# EDU_High-Speed-Design_Ethernet.net
KiCad netlist of a schematic drawn in Altium Designer
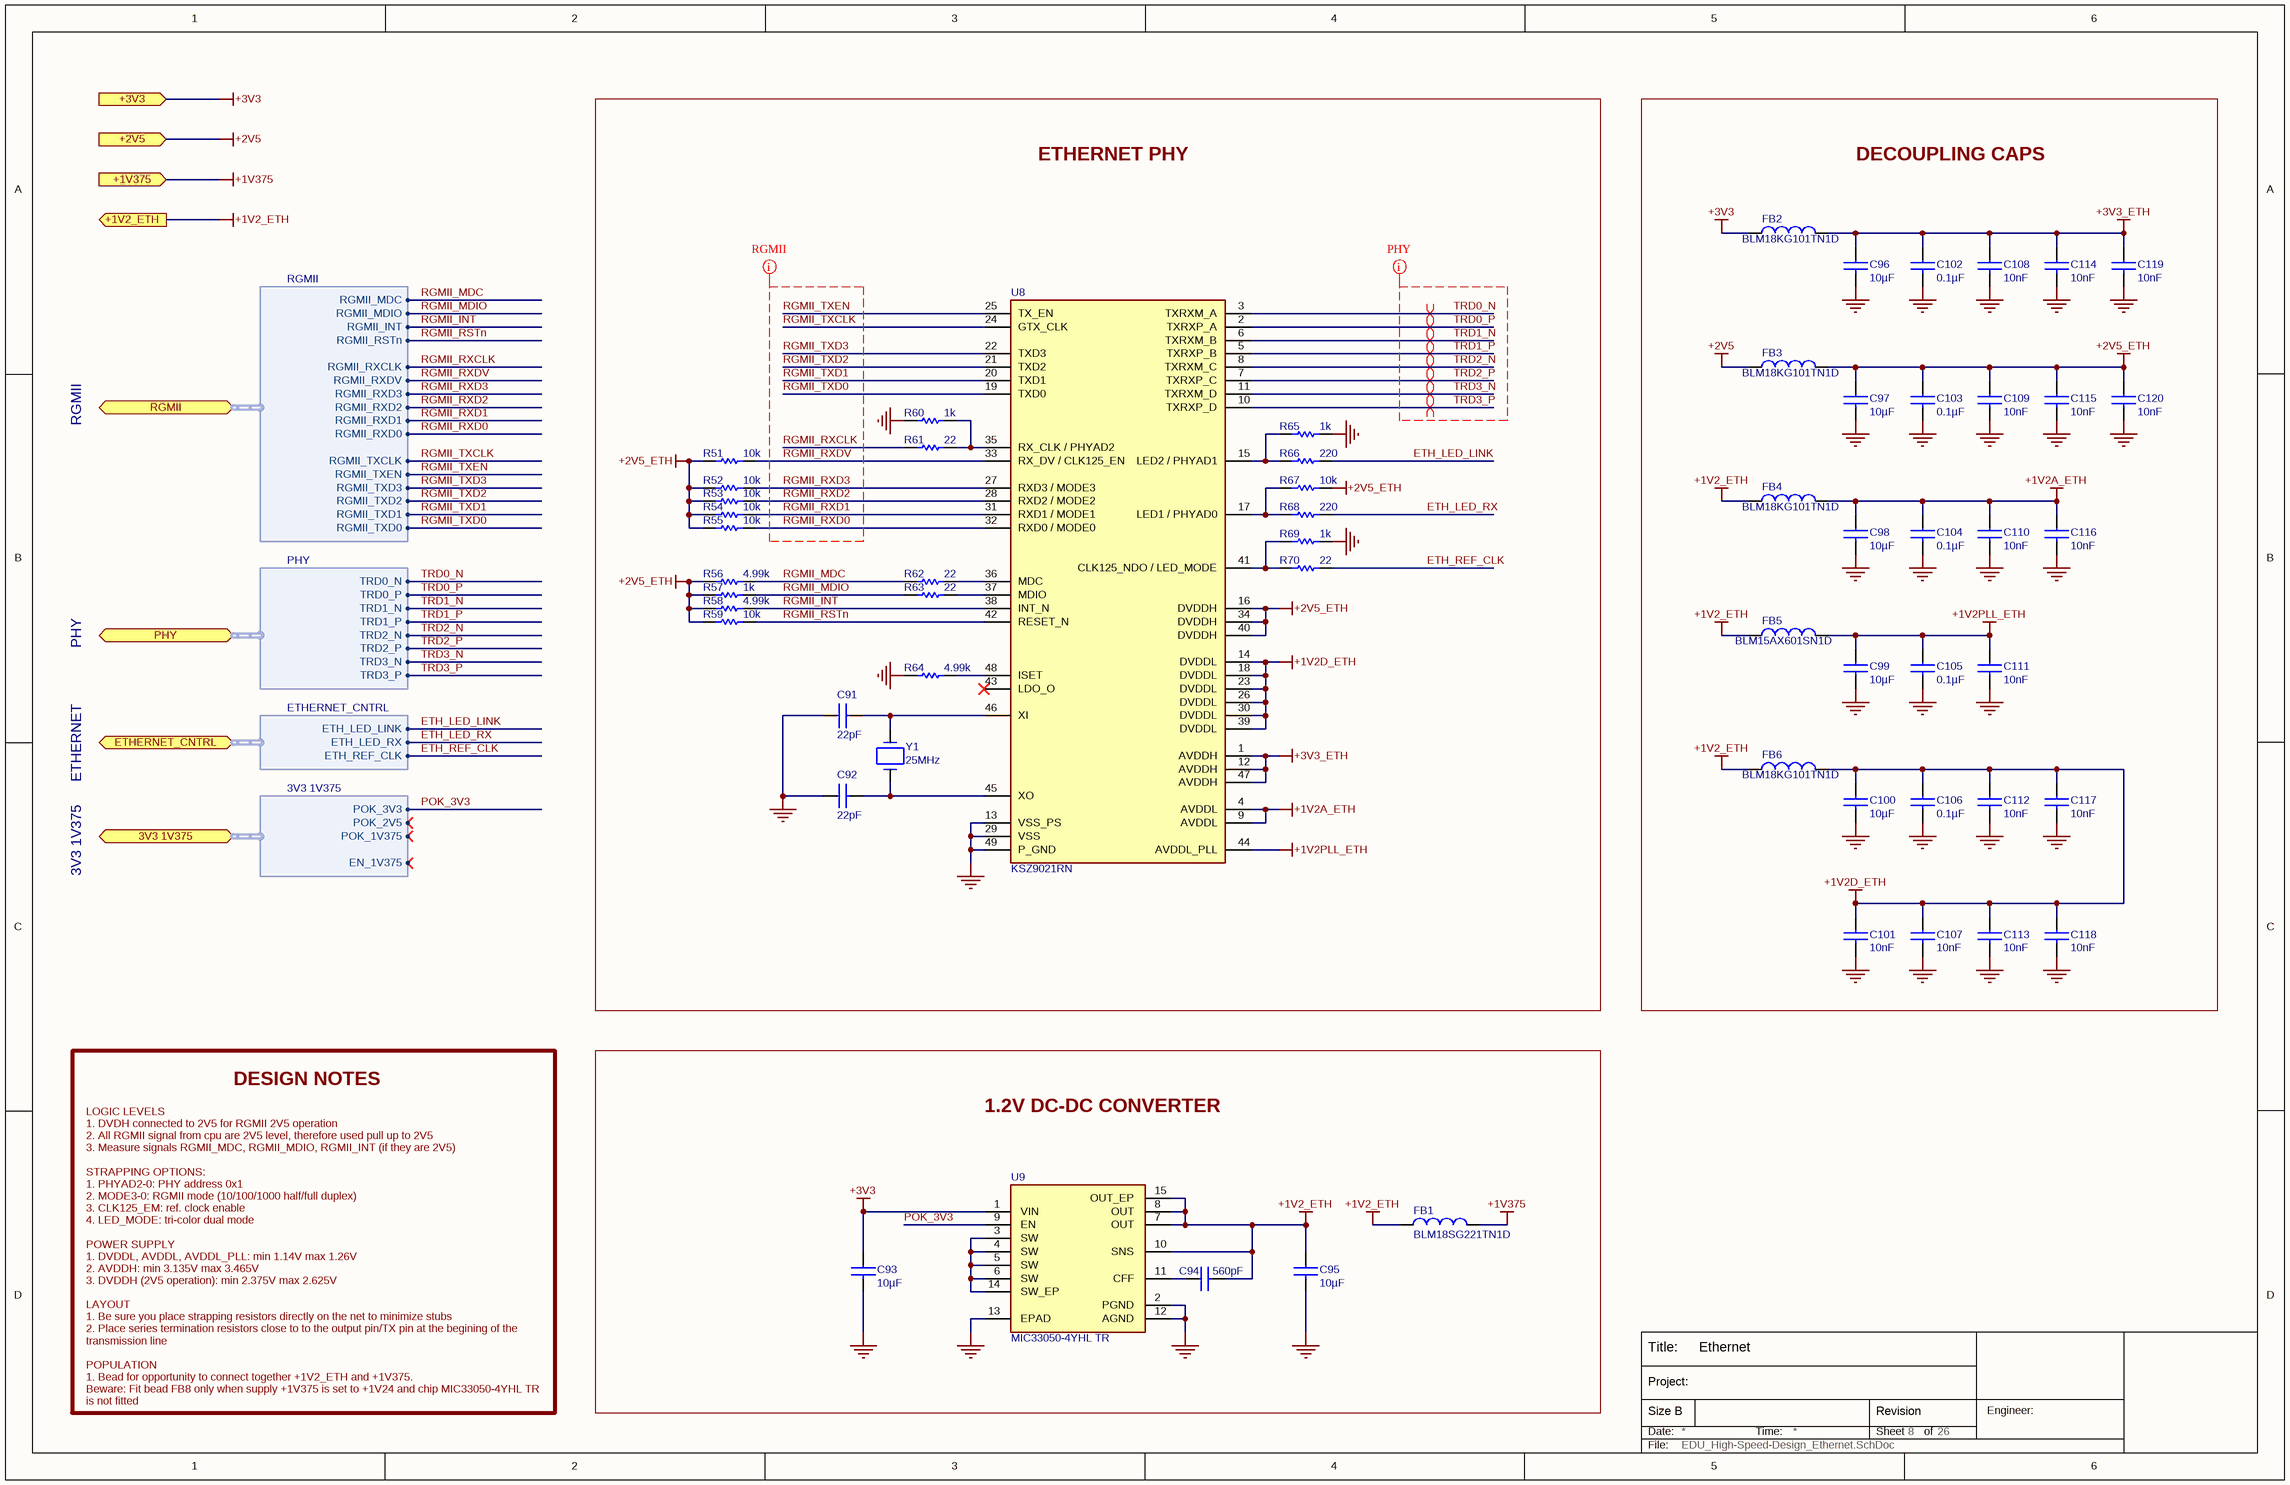
[diagram p0: EDU_High-Speed-Design_Ethernet.SchDoc]

(export (version "E")
  (design (tool "Eeschema 10.0.6"))
  (components
    (comp (ref "C91")
      (value "22pF")
      (footprint "C0402")
      (description "CAP CER 22PF 50V C0G 5% 0402")
      (fields (field (name "VOLTAGE") "50V"))
      (libsource (lib "EDU_High-Speed-Design") (part "C1005C0G1H220J"))
    )
    (comp (ref "C92")
      (value "22pF")
      (footprint "C0402")
      (description "CAP CER 22PF 50V C0G 5% 0402")
      (fields (field (name "VOLTAGE") "50V"))
      (libsource (lib "EDU_High-Speed-Design") (part "C1005C0G1H220J"))
    )
    (comp (ref "C93")
      (value "10µF")
      (footprint "C0603")
      (description "CAP CER 10UF 6.3V X5R 20% 0603")
      (fields (field (name "VOLTAGE") "6.3V"))
      (libsource (lib "EDU_High-Speed-Design") (part "C1608X5R0J106M"))
    )
    (comp (ref "C94")
      (value "560pF")
      (footprint "C0402")
      (description "CAP CER 560PF 50V C0G 0402")
      (fields (field (name "VOLTAGE") "50V"))
      (libsource (lib "EDU_High-Speed-Design") (part "GRM1555C1H561JA01D"))
    )
    (comp (ref "C95")
      (value "10µF")
      (footprint "C0603")
      (description "CAP CER 10UF 6.3V X5R 20% 0603")
      (fields (field (name "VOLTAGE") "6.3V"))
      (libsource (lib "EDU_High-Speed-Design") (part "C1608X5R0J106M"))
    )
    (comp (ref "C96")
      (value "10µF")
      (footprint "C0603")
      (description "CAP CER 10UF 6.3V X5R 20% 0603")
      (fields (field (name "VOLTAGE") "6.3V"))
      (libsource (lib "EDU_High-Speed-Design") (part "C1608X5R0J106M"))
    )
    (comp (ref "C97")
      (value "10µF")
      (footprint "C0603")
      (description "CAP CER 10UF 6.3V X5R 20% 0603")
      (fields (field (name "VOLTAGE") "6.3V"))
      (libsource (lib "EDU_High-Speed-Design") (part "C1608X5R0J106M"))
    )
    (comp (ref "C98")
      (value "10µF")
      (footprint "C0603")
      (description "CAP CER 10UF 6.3V X5R 20% 0603")
      (fields (field (name "VOLTAGE") "6.3V"))
      (libsource (lib "EDU_High-Speed-Design") (part "C1608X5R0J106M"))
    )
    (comp (ref "C99")
      (value "10µF")
      (footprint "C0603")
      (description "CAP CER 10UF 6.3V X5R 20% 0603")
      (fields (field (name "VOLTAGE") "6.3V"))
      (libsource (lib "EDU_High-Speed-Design") (part "C1608X5R0J106M"))
    )
    (comp (ref "C100")
      (value "10µF")
      (footprint "C0603")
      (description "CAP CER 10UF 6.3V X5R 20% 0603")
      (fields (field (name "VOLTAGE") "6.3V"))
      (libsource (lib "EDU_High-Speed-Design") (part "C1608X5R0J106M"))
    )
    (comp (ref "C101")
      (value "10nF")
      (footprint "C0402")
      (description "CAP CER 10000PF 16V X7R 10% 0402")
      (fields
        (field (name "MANUFACTURER") "TDK Corporation")
        (field (name "MANUFACTURER PART NUMBER") "C1005X7R1C103K")
      )
      (libsource (lib "EDU_High-Speed-Design") (part "C1005X7R1C103K"))
    )
    (comp (ref "C102")
      (value "0.1µF")
      (footprint "C0402")
      (description "CAP CER .10UF 50V X5R 10% 0402")
      (fields (field (name "VOLTAGE") "50V"))
      (libsource (lib "EDU_High-Speed-Design") (part "C1005X5R1H104K"))
    )
    (comp (ref "C103")
      (value "0.1µF")
      (footprint "C0402")
      (description "CAP CER .10UF 50V X5R 10% 0402")
      (fields (field (name "VOLTAGE") "50V"))
      (libsource (lib "EDU_High-Speed-Design") (part "C1005X5R1H104K"))
    )
    (comp (ref "C104")
      (value "0.1µF")
      (footprint "C0402")
      (description "CAP CER .10UF 50V X5R 10% 0402")
      (fields (field (name "VOLTAGE") "50V"))
      (libsource (lib "EDU_High-Speed-Design") (part "C1005X5R1H104K"))
    )
    (comp (ref "C105")
      (value "0.1µF")
      (footprint "C0402")
      (description "CAP CER .10UF 50V X5R 10% 0402")
      (fields (field (name "VOLTAGE") "50V"))
      (libsource (lib "EDU_High-Speed-Design") (part "C1005X5R1H104K"))
    )
    (comp (ref "C106")
      (value "0.1µF")
      (footprint "C0402")
      (description "CAP CER .10UF 50V X5R 10% 0402")
      (fields (field (name "VOLTAGE") "50V"))
      (libsource (lib "EDU_High-Speed-Design") (part "C1005X5R1H104K"))
    )
    (comp (ref "C107")
      (value "10nF")
      (footprint "C0402")
      (description "CAP CER 10000PF 16V X7R 10% 0402")
      (fields
        (field (name "MANUFACTURER") "TDK Corporation")
        (field (name "MANUFACTURER PART NUMBER") "C1005X7R1C103K")
      )
      (libsource (lib "EDU_High-Speed-Design") (part "C1005X7R1C103K"))
    )
    (comp (ref "C108")
      (value "10nF")
      (footprint "C0402")
      (description "CAP CER 10000PF 16V X7R 10% 0402")
      (fields
        (field (name "MANUFACTURER") "TDK Corporation")
        (field (name "MANUFACTURER PART NUMBER") "C1005X7R1C103K")
      )
      (libsource (lib "EDU_High-Speed-Design") (part "C1005X7R1C103K"))
    )
    (comp (ref "C109")
      (value "10nF")
      (footprint "C0402")
      (description "CAP CER 10000PF 16V X7R 10% 0402")
      (fields
        (field (name "MANUFACTURER") "TDK Corporation")
        (field (name "MANUFACTURER PART NUMBER") "C1005X7R1C103K")
      )
      (libsource (lib "EDU_High-Speed-Design") (part "C1005X7R1C103K"))
    )
    (comp (ref "C110")
      (value "10nF")
      (footprint "C0402")
      (description "CAP CER 10000PF 16V X7R 10% 0402")
      (fields
        (field (name "MANUFACTURER") "TDK Corporation")
        (field (name "MANUFACTURER PART NUMBER") "C1005X7R1C103K")
      )
      (libsource (lib "EDU_High-Speed-Design") (part "C1005X7R1C103K"))
    )
    (comp (ref "C111")
      (value "10nF")
      (footprint "C0402")
      (description "CAP CER 10000PF 16V X7R 10% 0402")
      (fields
        (field (name "MANUFACTURER") "TDK Corporation")
        (field (name "MANUFACTURER PART NUMBER") "C1005X7R1C103K")
      )
      (libsource (lib "EDU_High-Speed-Design") (part "C1005X7R1C103K"))
    )
    (comp (ref "C112")
      (value "10nF")
      (footprint "C0402")
      (description "CAP CER 10000PF 16V X7R 10% 0402")
      (fields
        (field (name "MANUFACTURER") "TDK Corporation")
        (field (name "MANUFACTURER PART NUMBER") "C1005X7R1C103K")
      )
      (libsource (lib "EDU_High-Speed-Design") (part "C1005X7R1C103K"))
    )
    (comp (ref "C113")
      (value "10nF")
      (footprint "C0402")
      (description "CAP CER 10000PF 16V X7R 10% 0402")
      (fields
        (field (name "MANUFACTURER") "TDK Corporation")
        (field (name "MANUFACTURER PART NUMBER") "C1005X7R1C103K")
      )
      (libsource (lib "EDU_High-Speed-Design") (part "C1005X7R1C103K"))
    )
    (comp (ref "C114")
      (value "10nF")
      (footprint "C0402")
      (description "CAP CER 10000PF 16V X7R 10% 0402")
      (fields
        (field (name "MANUFACTURER") "TDK Corporation")
        (field (name "MANUFACTURER PART NUMBER") "C1005X7R1C103K")
      )
      (libsource (lib "EDU_High-Speed-Design") (part "C1005X7R1C103K"))
    )
    (comp (ref "C115")
      (value "10nF")
      (footprint "C0402")
      (description "CAP CER 10000PF 16V X7R 10% 0402")
      (fields
        (field (name "MANUFACTURER") "TDK Corporation")
        (field (name "MANUFACTURER PART NUMBER") "C1005X7R1C103K")
      )
      (libsource (lib "EDU_High-Speed-Design") (part "C1005X7R1C103K"))
    )
    (comp (ref "C116")
      (value "10nF")
      (footprint "C0402")
      (description "CAP CER 10000PF 16V X7R 10% 0402")
      (fields
        (field (name "MANUFACTURER") "TDK Corporation")
        (field (name "MANUFACTURER PART NUMBER") "C1005X7R1C103K")
      )
      (libsource (lib "EDU_High-Speed-Design") (part "C1005X7R1C103K"))
    )
    (comp (ref "C117")
      (value "10nF")
      (footprint "C0402")
      (description "CAP CER 10000PF 16V X7R 10% 0402")
      (fields
        (field (name "MANUFACTURER") "TDK Corporation")
        (field (name "MANUFACTURER PART NUMBER") "C1005X7R1C103K")
      )
      (libsource (lib "EDU_High-Speed-Design") (part "C1005X7R1C103K"))
    )
    (comp (ref "C118")
      (value "10nF")
      (footprint "C0402")
      (description "CAP CER 10000PF 16V X7R 10% 0402")
      (fields
        (field (name "MANUFACTURER") "TDK Corporation")
        (field (name "MANUFACTURER PART NUMBER") "C1005X7R1C103K")
      )
      (libsource (lib "EDU_High-Speed-Design") (part "C1005X7R1C103K"))
    )
    (comp (ref "C119")
      (value "10nF")
      (footprint "C0402")
      (description "CAP CER 10000PF 16V X7R 10% 0402")
      (fields
        (field (name "MANUFACTURER") "TDK Corporation")
        (field (name "MANUFACTURER PART NUMBER") "C1005X7R1C103K")
      )
      (libsource (lib "EDU_High-Speed-Design") (part "C1005X7R1C103K"))
    )
    (comp (ref "C120")
      (value "10nF")
      (footprint "C0402")
      (description "CAP CER 10000PF 16V X7R 10% 0402")
      (fields
        (field (name "MANUFACTURER") "TDK Corporation")
        (field (name "MANUFACTURER PART NUMBER") "C1005X7R1C103K")
      )
      (libsource (lib "EDU_High-Speed-Design") (part "C1005X7R1C103K"))
    )
    (comp (ref "FB1")
      (value "BLM18SG221TN1D")
      (footprint "L0603")
      (description "FERRITE CHIP 220 OHM 2500MA 0603")
      (libsource (lib "EDU_High-Speed-Design") (part "BLM18SG221TN1D"))
    )
    (comp (ref "FB2")
      (value "BLM18KG101TN1D")
      (footprint "L0603")
      (description "FERRITE CHIP 100 OHM BEAD 0603 3A")
      (libsource (lib "EDU_High-Speed-Design") (part "BLM18KG101TN1D"))
    )
    (comp (ref "FB3")
      (value "BLM18KG101TN1D")
      (footprint "L0603")
      (description "FERRITE CHIP 100 OHM BEAD 0603 3A")
      (libsource (lib "EDU_High-Speed-Design") (part "BLM18KG101TN1D"))
    )
    (comp (ref "FB4")
      (value "BLM18KG101TN1D")
      (footprint "L0603")
      (description "FERRITE CHIP 100 OHM BEAD 0603 3A")
      (libsource (lib "EDU_High-Speed-Design") (part "BLM18KG101TN1D"))
    )
    (comp (ref "FB5")
      (value "BLM15AX601SN1D")
      (footprint "L0402")
      (description "FERRITE CHIP 600 OHM 0402 420mA")
      (libsource (lib "EDU_High-Speed-Design") (part "BLM15AX601SN1D"))
    )
    (comp (ref "FB6")
      (value "BLM18KG101TN1D")
      (footprint "L0603")
      (description "FERRITE CHIP 100 OHM BEAD 0603 3A")
      (libsource (lib "EDU_High-Speed-Design") (part "BLM18KG101TN1D"))
    )
    (comp (ref "R51")
      (value "10k")
      (footprint "R0402")
      (description "RES 10.0K OHM 1/16W 1% 0402 SMD")
      (libsource (lib "EDU_High-Speed-Design") (part "RC0402FR-0710KL"))
    )
    (comp (ref "R52")
      (value "10k")
      (footprint "R0402")
      (description "RES 10.0K OHM 1/16W 1% 0402 SMD")
      (libsource (lib "EDU_High-Speed-Design") (part "RC0402FR-0710KL"))
    )
    (comp (ref "R53")
      (value "10k")
      (footprint "R0402")
      (description "RES 10.0K OHM 1/16W 1% 0402 SMD")
      (libsource (lib "EDU_High-Speed-Design") (part "RC0402FR-0710KL"))
    )
    (comp (ref "R54")
      (value "10k")
      (footprint "R0402")
      (description "RES 10.0K OHM 1/16W 1% 0402 SMD")
      (libsource (lib "EDU_High-Speed-Design") (part "RC0402FR-0710KL"))
    )
    (comp (ref "R55")
      (value "10k")
      (footprint "R0402")
      (description "RES 10.0K OHM 1/16W 1% 0402 SMD")
      (libsource (lib "EDU_High-Speed-Design") (part "RC0402FR-0710KL"))
    )
    (comp (ref "R56")
      (value "4.99k")
      (footprint "R0402")
      (description "RES TF 4.99K OHM 1% 1/16W 0402")
      (libsource (lib "EDU_High-Speed-Design") (part "RMCF0402FT4K99"))
    )
    (comp (ref "R57")
      (value "1k")
      (footprint "R0402")
      (description "RES 1.00K OHM 1/16W 1% 0402 SMD")
      (libsource (lib "EDU_High-Speed-Design") (part "RC0402FR-071KL"))
    )
    (comp (ref "R58")
      (value "4.99k")
      (footprint "R0402")
      (description "RES TF 4.99K OHM 1% 1/16W 0402")
      (libsource (lib "EDU_High-Speed-Design") (part "RMCF0402FT4K99"))
    )
    (comp (ref "R59")
      (value "10k")
      (footprint "R0402")
      (description "RES 10.0K OHM 1/16W 1% 0402 SMD")
      (libsource (lib "EDU_High-Speed-Design") (part "RC0402FR-0710KL"))
    )
    (comp (ref "R60")
      (value "1k")
      (footprint "R0402")
      (description "RES 1.00K OHM 1/16W 1% 0402 SMD")
      (libsource (lib "EDU_High-Speed-Design") (part "RC0402FR-071KL"))
    )
    (comp (ref "R61")
      (value "22")
      (footprint "R0402")
      (description "RES 22.0 OHM 1/16W 1% 0402 SMD")
      (libsource (lib "EDU_High-Speed-Design") (part "RC0402FR-0722RL"))
    )
    (comp (ref "R62")
      (value "22")
      (footprint "R0402")
      (description "RES 22.0 OHM 1/16W 1% 0402 SMD")
      (libsource (lib "EDU_High-Speed-Design") (part "RC0402FR-0722RL"))
    )
    (comp (ref "R63")
      (value "22")
      (footprint "R0402")
      (description "RES 22.0 OHM 1/16W 1% 0402 SMD")
      (libsource (lib "EDU_High-Speed-Design") (part "RC0402FR-0722RL"))
    )
    (comp (ref "R64")
      (value "4.99k")
      (footprint "R0402")
      (description "RES TF 4.99K OHM 1% 1/16W 0402")
      (libsource (lib "EDU_High-Speed-Design") (part "RMCF0402FT4K99"))
    )
    (comp (ref "R65")
      (value "1k")
      (footprint "R0402")
      (description "RES 1.00K OHM 1/16W 1% 0402 SMD")
      (libsource (lib "EDU_High-Speed-Design") (part "RC0402FR-071KL"))
    )
    (comp (ref "R66")
      (value "220")
      (footprint "R0402")
      (description "RES 220 OHM 1/16W 1% 0402 SMD")
      (libsource (lib "EDU_High-Speed-Design") (part "RC0402FR-07220RL"))
    )
    (comp (ref "R67")
      (value "10k")
      (footprint "R0402")
      (description "RES 10.0K OHM 1/16W 1% 0402 SMD")
      (libsource (lib "EDU_High-Speed-Design") (part "RC0402FR-0710KL"))
    )
    (comp (ref "R68")
      (value "220")
      (footprint "R0402")
      (description "RES 220 OHM 1/16W 1% 0402 SMD")
      (libsource (lib "EDU_High-Speed-Design") (part "RC0402FR-07220RL"))
    )
    (comp (ref "R69")
      (value "1k")
      (footprint "R0402")
      (description "RES 1.00K OHM 1/16W 1% 0402 SMD")
      (libsource (lib "EDU_High-Speed-Design") (part "RC0402FR-071KL"))
    )
    (comp (ref "R70")
      (value "22")
      (footprint "R0402")
      (description "RES 22.0 OHM 1/16W 1% 0402 SMD")
      (libsource (lib "EDU_High-Speed-Design") (part "RC0402FR-0722RL"))
    )
    (comp (ref "U8")
      (value "KSZ9021RN")
      (footprint "KSZ9021RN")
      (description "IC TXRX 10/100/1000 SGL 48QFN")
      (libsource (lib "EDU_High-Speed-Design") (part "KSZ9021RN"))
    )
    (comp (ref "U9")
      (value "MIC33050-4YHL TR")
      (footprint "MIC33050-4YHL TR")
      (description "IC PWM REG 600mA 1.2V 12-MLF")
      (libsource (lib "EDU_High-Speed-Design") (part "MIC33050-4YHL TR"))
    )
    (comp (ref "Y1")
      (value "25MHz")
      (footprint "ABM7")
      (description "CRYSTAL 25.0000 MHZ 18PF SMD")
      (libsource (lib "EDU_High-Speed-Design") (part "ABM7-25.000MHZ-D-2-Y-T V1.1"))
    )
  )
  (nets
    (net (code "6") (name "+1V2A_ETH") (class "Default")
      (node (ref "C104") (pin "1") (pinfunction "1_1") (pintype "passive"))
      (node (ref "C110") (pin "1") (pinfunction "1_1") (pintype "passive"))
      (node (ref "C116") (pin "1") (pinfunction "1_1") (pintype "passive"))
      (node (ref "C98") (pin "1") (pinfunction "1_1") (pintype "passive"))
      (node (ref "FB4") (pin "2") (pinfunction "2_2") (pintype "passive"))
      (node (ref "U8") (pin "4") (pinfunction "AVDDL_4") (pintype "passive"))
      (node (ref "U8") (pin "9") (pinfunction "AVDDL_9") (pintype "passive"))
    )
    (net (code "7") (name "+1V2D_ETH") (class "Default")
      (node (ref "C100") (pin "1") (pinfunction "1_1") (pintype "passive"))
      (node (ref "C101") (pin "1") (pinfunction "1_1") (pintype "passive"))
      (node (ref "C106") (pin "1") (pinfunction "1_1") (pintype "passive"))
      (node (ref "C107") (pin "1") (pinfunction "1_1") (pintype "passive"))
      (node (ref "C112") (pin "1") (pinfunction "1_1") (pintype "passive"))
      (node (ref "C113") (pin "1") (pinfunction "1_1") (pintype "passive"))
      (node (ref "C117") (pin "1") (pinfunction "1_1") (pintype "passive"))
      (node (ref "C118") (pin "1") (pinfunction "1_1") (pintype "passive"))
      (node (ref "FB6") (pin "2") (pinfunction "2_2") (pintype "passive"))
      (node (ref "U8") (pin "14") (pinfunction "DVDDL_14") (pintype "passive"))
      (node (ref "U8") (pin "18") (pinfunction "DVDDL_18") (pintype "passive"))
      (node (ref "U8") (pin "23") (pinfunction "DVDDL_23") (pintype "passive"))
      (node (ref "U8") (pin "26") (pinfunction "DVDDL_26") (pintype "passive"))
      (node (ref "U8") (pin "30") (pinfunction "DVDDL_30") (pintype "passive"))
      (node (ref "U8") (pin "39") (pinfunction "DVDDL_39") (pintype "passive"))
    )
    (net (code "8") (name "+1V2PLL_ETH") (class "Default")
      (node (ref "C105") (pin "1") (pinfunction "1_1") (pintype "passive"))
      (node (ref "C111") (pin "1") (pinfunction "1_1") (pintype "passive"))
      (node (ref "C99") (pin "1") (pinfunction "1_1") (pintype "passive"))
      (node (ref "FB5") (pin "2") (pinfunction "2_2") (pintype "passive"))
      (node (ref "U8") (pin "44") (pinfunction "AVDDL_PLL_44") (pintype "passive"))
    )
    (net (code "9") (name "+1V2_ETH") (class "Default")
      (node (ref "C94") (pin "2") (pinfunction "2_2") (pintype "passive"))
      (node (ref "C95") (pin "1") (pinfunction "1_1") (pintype "passive"))
      (node (ref "FB1") (pin "1") (pinfunction "1_1") (pintype "passive"))
      (node (ref "FB4") (pin "1") (pinfunction "1_1") (pintype "passive"))
      (node (ref "FB5") (pin "1") (pinfunction "1_1") (pintype "passive"))
      (node (ref "FB6") (pin "1") (pinfunction "1_1") (pintype "passive"))
      (node (ref "U9") (pin "10") (pinfunction "SNS_10") (pintype "passive"))
      (node (ref "U9") (pin "15") (pinfunction "OUT_EP_15") (pintype "passive"))
      (node (ref "U9") (pin "7") (pinfunction "OUT_7") (pintype "passive"))
      (node (ref "U9") (pin "8") (pinfunction "OUT_8") (pintype "passive"))
    )
    (net (code "10") (name "+1V375") (class "Default")
      (node (ref "FB1") (pin "2") (pinfunction "2_2") (pintype "passive"))
    )
    (net (code "11") (name "+2V5") (class "Default")
      (node (ref "FB3") (pin "1") (pinfunction "1_1") (pintype "passive"))
    )
    (net (code "12") (name "+2V5_ETH") (class "Default")
      (node (ref "C103") (pin "1") (pinfunction "1_1") (pintype "passive"))
      (node (ref "C109") (pin "1") (pinfunction "1_1") (pintype "passive"))
      (node (ref "C115") (pin "1") (pinfunction "1_1") (pintype "passive"))
      (node (ref "C120") (pin "1") (pinfunction "1_1") (pintype "passive"))
      (node (ref "C97") (pin "1") (pinfunction "1_1") (pintype "passive"))
      (node (ref "FB3") (pin "2") (pinfunction "2_2") (pintype "passive"))
      (node (ref "R51") (pin "1") (pinfunction "1_1") (pintype "passive"))
      (node (ref "R52") (pin "1") (pinfunction "1_1") (pintype "passive"))
      (node (ref "R53") (pin "1") (pinfunction "1_1") (pintype "passive"))
      (node (ref "R54") (pin "1") (pinfunction "1_1") (pintype "passive"))
      (node (ref "R55") (pin "1") (pinfunction "1_1") (pintype "passive"))
      (node (ref "R56") (pin "2") (pinfunction "2_2") (pintype "passive"))
      (node (ref "R57") (pin "2") (pinfunction "2_2") (pintype "passive"))
      (node (ref "R58") (pin "2") (pinfunction "2_2") (pintype "passive"))
      (node (ref "R59") (pin "1") (pinfunction "1_1") (pintype "passive"))
      (node (ref "R67") (pin "2") (pinfunction "2_2") (pintype "passive"))
      (node (ref "U8") (pin "16") (pinfunction "DVDDH_16") (pintype "passive"))
      (node (ref "U8") (pin "34") (pinfunction "DVDDH_34") (pintype "passive"))
      (node (ref "U8") (pin "40") (pinfunction "DVDDH_40") (pintype "passive"))
    )
    (net (code "13") (name "+3V3") (class "Default")
      (node (ref "C93") (pin "1") (pinfunction "1_1") (pintype "passive"))
      (node (ref "FB2") (pin "1") (pinfunction "1_1") (pintype "passive"))
      (node (ref "U9") (pin "1") (pinfunction "VIN_1") (pintype "passive"))
    )
    (net (code "14") (name "+3V3_ETH") (class "Default")
      (node (ref "C102") (pin "1") (pinfunction "1_1") (pintype "passive"))
      (node (ref "C108") (pin "1") (pinfunction "1_1") (pintype "passive"))
      (node (ref "C114") (pin "1") (pinfunction "1_1") (pintype "passive"))
      (node (ref "C119") (pin "1") (pinfunction "1_1") (pintype "passive"))
      (node (ref "C96") (pin "1") (pinfunction "1_1") (pintype "passive"))
      (node (ref "FB2") (pin "2") (pinfunction "2_2") (pintype "passive"))
      (node (ref "U8") (pin "1") (pinfunction "AVDDH_1") (pintype "passive"))
      (node (ref "U8") (pin "12") (pinfunction "AVDDH_12") (pintype "passive"))
      (node (ref "U8") (pin "47") (pinfunction "AVDDH_47") (pintype "passive"))
    )
    (net (code "15") (name "/ETH_LED_LINK") (class "Default")
      (node (ref "R66") (pin "1") (pinfunction "1_1") (pintype "passive"))
    )
    (net (code "16") (name "/ETH_LED_RX") (class "Default")
      (node (ref "R68") (pin "1") (pinfunction "1_1") (pintype "passive"))
    )
    (net (code "17") (name "/ETH_REF_CLK") (class "Default")
      (node (ref "R70") (pin "1") (pinfunction "1_1") (pintype "passive"))
    )
    (net (code "18") (name "/POK_3V3") (class "Default")
      (node (ref "U9") (pin "9") (pinfunction "EN_9") (pintype "passive"))
    )
    (net (code "19") (name "/RGMII_INT") (class "Default")
      (node (ref "R58") (pin "1") (pinfunction "1_1") (pintype "passive"))
      (node (ref "U8") (pin "38") (pinfunction "INT_N_38") (pintype "passive"))
    )
    (net (code "20") (name "/RGMII_MDC") (class "Default")
      (node (ref "R56") (pin "1") (pinfunction "1_1") (pintype "passive"))
      (node (ref "R62") (pin "2") (pinfunction "2_2") (pintype "passive"))
    )
    (net (code "21") (name "/RGMII_MDIO") (class "Default")
      (node (ref "R57") (pin "1") (pinfunction "1_1") (pintype "passive"))
      (node (ref "R63") (pin "2") (pinfunction "2_2") (pintype "passive"))
    )
    (net (code "22") (name "/RGMII_RSTn") (class "Default")
      (node (ref "R59") (pin "2") (pinfunction "2_2") (pintype "passive"))
      (node (ref "U8") (pin "42") (pinfunction "RESET_N_42") (pintype "passive"))
    )
    (net (code "23") (name "/RGMII_RXCLK") (class "Default")
      (node (ref "R61") (pin "2") (pinfunction "2_2") (pintype "passive"))
    )
    (net (code "24") (name "/RGMII_RXD0") (class "Default")
      (node (ref "R55") (pin "2") (pinfunction "2_2") (pintype "passive"))
      (node (ref "U8") (pin "32") (pinfunction "RXD0_/_MODE0_32") (pintype "passive"))
    )
    (net (code "25") (name "/RGMII_RXD1") (class "Default")
      (node (ref "R54") (pin "2") (pinfunction "2_2") (pintype "passive"))
      (node (ref "U8") (pin "31") (pinfunction "RXD1_/_MODE1_31") (pintype "passive"))
    )
    (net (code "26") (name "/RGMII_RXD2") (class "Default")
      (node (ref "R53") (pin "2") (pinfunction "2_2") (pintype "passive"))
      (node (ref "U8") (pin "28") (pinfunction "RXD2_/_MODE2_28") (pintype "passive"))
    )
    (net (code "27") (name "/RGMII_RXD3") (class "Default")
      (node (ref "R52") (pin "2") (pinfunction "2_2") (pintype "passive"))
      (node (ref "U8") (pin "27") (pinfunction "RXD3_/_MODE3_27") (pintype "passive"))
    )
    (net (code "28") (name "/RGMII_RXDV") (class "Default")
      (node (ref "R51") (pin "2") (pinfunction "2_2") (pintype "passive"))
      (node (ref "U8") (pin "33") (pinfunction "RX_DV_/_CLK125_EN_33") (pintype "passive"))
    )
    (net (code "29") (name "/RGMII_TXCLK") (class "Default")
      (node (ref "U8") (pin "24") (pinfunction "GTX_CLK_24") (pintype "passive"))
    )
    (net (code "30") (name "/RGMII_TXD0") (class "Default")
      (node (ref "U8") (pin "19") (pinfunction "TXD0_19") (pintype "passive"))
    )
    (net (code "31") (name "/RGMII_TXD1") (class "Default")
      (node (ref "U8") (pin "20") (pinfunction "TXD1_20") (pintype "passive"))
    )
    (net (code "32") (name "/RGMII_TXD2") (class "Default")
      (node (ref "U8") (pin "21") (pinfunction "TXD2_21") (pintype "passive"))
    )
    (net (code "33") (name "/RGMII_TXD3") (class "Default")
      (node (ref "U8") (pin "22") (pinfunction "TXD3_22") (pintype "passive"))
    )
    (net (code "34") (name "/RGMII_TXEN") (class "Default")
      (node (ref "U8") (pin "25") (pinfunction "TX_EN_25") (pintype "passive"))
    )
    (net (code "35") (name "/TRD0_N") (class "Default")
      (node (ref "U8") (pin "3") (pinfunction "TXRXM_A_3") (pintype "passive"))
    )
    (net (code "36") (name "/TRD0_P") (class "Default")
      (node (ref "U8") (pin "2") (pinfunction "TXRXP_A_2") (pintype "passive"))
    )
    (net (code "37") (name "/TRD1_N") (class "Default")
      (node (ref "U8") (pin "6") (pinfunction "TXRXM_B_6") (pintype "passive"))
    )
    (net (code "38") (name "/TRD1_P") (class "Default")
      (node (ref "U8") (pin "5") (pinfunction "TXRXP_B_5") (pintype "passive"))
    )
    (net (code "39") (name "/TRD2_N") (class "Default")
      (node (ref "U8") (pin "8") (pinfunction "TXRXM_C_8") (pintype "passive"))
    )
    (net (code "40") (name "/TRD2_P") (class "Default")
      (node (ref "U8") (pin "7") (pinfunction "TXRXP_C_7") (pintype "passive"))
    )
    (net (code "41") (name "/TRD3_N") (class "Default")
      (node (ref "U8") (pin "11") (pinfunction "TXRXM_D_11") (pintype "passive"))
    )
    (net (code "42") (name "/TRD3_P") (class "Default")
      (node (ref "U8") (pin "10") (pinfunction "TXRXP_D_10") (pintype "passive"))
    )
    (net (code "47") (name "GND") (class "Default")
      (node (ref "C100") (pin "2") (pinfunction "2_2") (pintype "passive"))
      (node (ref "C101") (pin "2") (pinfunction "2_2") (pintype "passive"))
      (node (ref "C102") (pin "2") (pinfunction "2_2") (pintype "passive"))
      (node (ref "C103") (pin "2") (pinfunction "2_2") (pintype "passive"))
      (node (ref "C104") (pin "2") (pinfunction "2_2") (pintype "passive"))
      (node (ref "C105") (pin "2") (pinfunction "2_2") (pintype "passive"))
      (node (ref "C106") (pin "2") (pinfunction "2_2") (pintype "passive"))
      (node (ref "C107") (pin "2") (pinfunction "2_2") (pintype "passive"))
      (node (ref "C108") (pin "2") (pinfunction "2_2") (pintype "passive"))
      (node (ref "C109") (pin "2") (pinfunction "2_2") (pintype "passive"))
      (node (ref "C110") (pin "2") (pinfunction "2_2") (pintype "passive"))
      (node (ref "C111") (pin "2") (pinfunction "2_2") (pintype "passive"))
      (node (ref "C112") (pin "2") (pinfunction "2_2") (pintype "passive"))
      (node (ref "C113") (pin "2") (pinfunction "2_2") (pintype "passive"))
      (node (ref "C114") (pin "2") (pinfunction "2_2") (pintype "passive"))
      (node (ref "C115") (pin "2") (pinfunction "2_2") (pintype "passive"))
      (node (ref "C116") (pin "2") (pinfunction "2_2") (pintype "passive"))
      (node (ref "C117") (pin "2") (pinfunction "2_2") (pintype "passive"))
      (node (ref "C118") (pin "2") (pinfunction "2_2") (pintype "passive"))
      (node (ref "C119") (pin "2") (pinfunction "2_2") (pintype "passive"))
      (node (ref "C120") (pin "2") (pinfunction "2_2") (pintype "passive"))
      (node (ref "C91") (pin "1") (pinfunction "1_1") (pintype "passive"))
      (node (ref "C92") (pin "1") (pinfunction "1_1") (pintype "passive"))
      (node (ref "C93") (pin "2") (pinfunction "2_2") (pintype "passive"))
      (node (ref "C95") (pin "2") (pinfunction "2_2") (pintype "passive"))
      (node (ref "C96") (pin "2") (pinfunction "2_2") (pintype "passive"))
      (node (ref "C97") (pin "2") (pinfunction "2_2") (pintype "passive"))
      (node (ref "C98") (pin "2") (pinfunction "2_2") (pintype "passive"))
      (node (ref "C99") (pin "2") (pinfunction "2_2") (pintype "passive"))
      (node (ref "R60") (pin "2") (pinfunction "2_2") (pintype "passive"))
      (node (ref "R64") (pin "2") (pinfunction "2_2") (pintype "passive"))
      (node (ref "R65") (pin "1") (pinfunction "1_1") (pintype "passive"))
      (node (ref "R69") (pin "1") (pinfunction "1_1") (pintype "passive"))
      (node (ref "U8") (pin "13") (pinfunction "VSS_PS_13") (pintype "passive"))
      (node (ref "U8") (pin "29") (pinfunction "VSS_29") (pintype "passive"))
      (node (ref "U8") (pin "49") (pinfunction "P_GND_49") (pintype "passive"))
      (node (ref "U9") (pin "12") (pinfunction "AGND_12") (pintype "passive"))
      (node (ref "U9") (pin "13") (pinfunction "EPAD_13") (pintype "passive"))
      (node (ref "U9") (pin "2") (pinfunction "PGND_2") (pintype "passive"))
    )
    (net (code "48") (name "Net-(U8-CLK125_NDO_{slash}_LED_MODE)") (class "Default")
      (node (ref "R69") (pin "2") (pinfunction "2_2") (pintype "passive"))
      (node (ref "R70") (pin "2") (pinfunction "2_2") (pintype "passive"))
      (node (ref "U8") (pin "41") (pinfunction "CLK125_NDO_/_LED_MODE_41") (pintype "passive"))
    )
    (net (code "49") (name "Net-(U8-ISET)") (class "Default")
      (node (ref "R64") (pin "1") (pinfunction "1_1") (pintype "passive"))
      (node (ref "U8") (pin "48") (pinfunction "ISET_48") (pintype "passive"))
    )
    (net (code "50") (name "Net-(U8-LED1_{slash}_PHYAD0)") (class "Default")
      (node (ref "R67") (pin "1") (pinfunction "1_1") (pintype "passive"))
      (node (ref "R68") (pin "2") (pinfunction "2_2") (pintype "passive"))
      (node (ref "U8") (pin "17") (pinfunction "LED1_/_PHYAD0_17") (pintype "passive"))
    )
    (net (code "51") (name "Net-(U8-LED2_{slash}_PHYAD1)") (class "Default")
      (node (ref "R65") (pin "2") (pinfunction "2_2") (pintype "passive"))
      (node (ref "R66") (pin "2") (pinfunction "2_2") (pintype "passive"))
      (node (ref "U8") (pin "15") (pinfunction "LED2_/_PHYAD1_15") (pintype "passive"))
    )
    (net (code "52") (name "Net-(U8-MDC)") (class "Default")
      (node (ref "R62") (pin "1") (pinfunction "1_1") (pintype "passive"))
      (node (ref "U8") (pin "36") (pinfunction "MDC_36") (pintype "passive"))
    )
    (net (code "53") (name "Net-(U8-MDIO)") (class "Default")
      (node (ref "R63") (pin "1") (pinfunction "1_1") (pintype "passive"))
      (node (ref "U8") (pin "37") (pinfunction "MDIO_37") (pintype "passive"))
    )
    (net (code "54") (name "Net-(U8-RX_CLK_{slash}_PHYAD2)") (class "Default")
      (node (ref "R60") (pin "1") (pinfunction "1_1") (pintype "passive"))
      (node (ref "R61") (pin "1") (pinfunction "1_1") (pintype "passive"))
      (node (ref "U8") (pin "35") (pinfunction "RX_CLK_/_PHYAD2_35") (pintype "passive"))
    )
    (net (code "55") (name "Net-(U8-XI)") (class "Default")
      (node (ref "C91") (pin "2") (pinfunction "2_2") (pintype "passive"))
      (node (ref "U8") (pin "46") (pinfunction "XI_46") (pintype "passive"))
      (node (ref "Y1") (pin "2") (pinfunction "2_2") (pintype "passive"))
    )
    (net (code "56") (name "Net-(U8-XO)") (class "Default")
      (node (ref "C92") (pin "2") (pinfunction "2_2") (pintype "passive"))
      (node (ref "U8") (pin "45") (pinfunction "XO_45") (pintype "passive"))
      (node (ref "Y1") (pin "1") (pinfunction "1_1") (pintype "passive"))
    )
    (net (code "57") (name "Net-(U9-CFF)") (class "Default")
      (node (ref "C94") (pin "1") (pinfunction "1_1") (pintype "passive"))
      (node (ref "U9") (pin "11") (pinfunction "CFF_11") (pintype "passive"))
    )
    (net (code "58") (name "Net-(U9-SW_EP)") (class "Default")
      (node (ref "U9") (pin "14") (pinfunction "SW_EP_14") (pintype "passive"))
      (node (ref "U9") (pin "3") (pinfunction "SW_3") (pintype "passive"))
      (node (ref "U9") (pin "4") (pinfunction "SW_4") (pintype "passive"))
      (node (ref "U9") (pin "5") (pinfunction "SW_5") (pintype "passive"))
      (node (ref "U9") (pin "6") (pinfunction "SW_6") (pintype "passive"))
    )
    (net (code "59") (name "unconnected-(U8-LDO_O-Pad43)") (class "Default")
      (node (ref "U8") (pin "43") (pinfunction "LDO_O_43") (pintype "passive+no_connect"))
    )
  )
)
